# vcsklpf.net
KiCad netlist of a schematic drawn in EAGLE
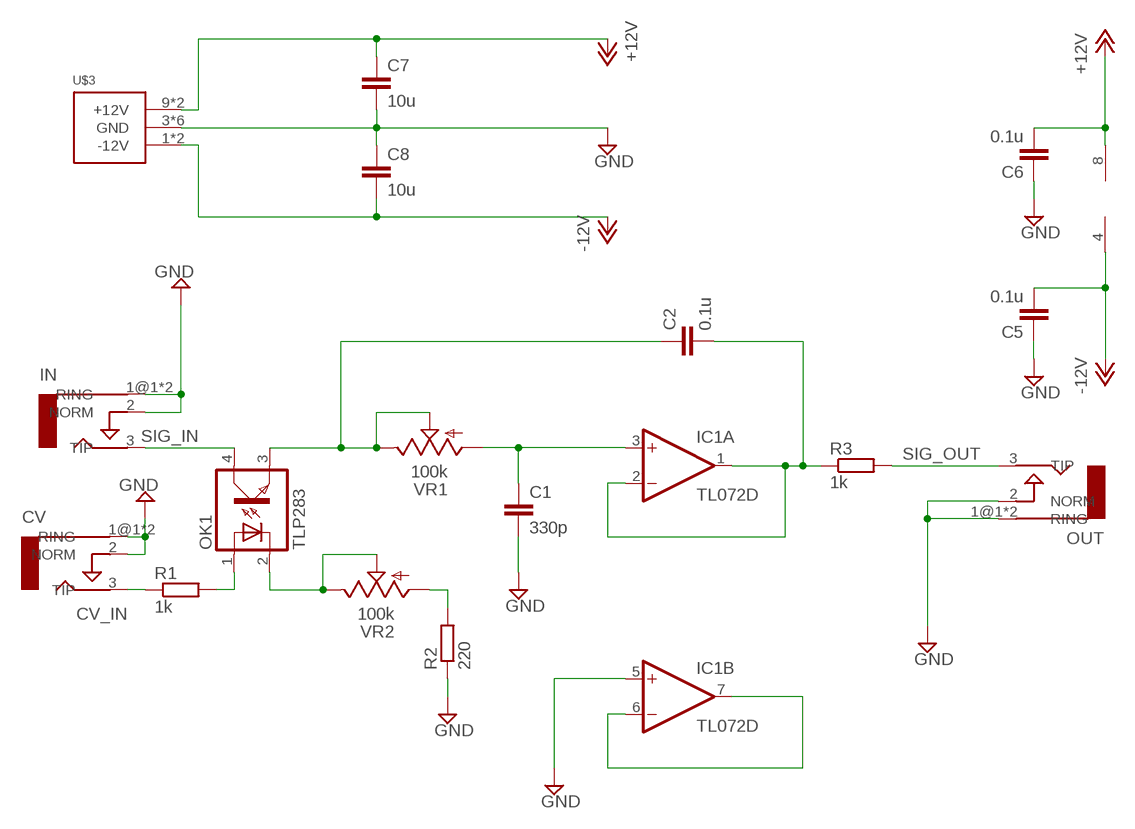
[diagram p0: schematic, sheet 1]

(export (version "E")
  (design (tool "Eeschema 10.0.6"))
  (components
    (comp (ref "C1")
      (value "330p")
      (footprint "eagle-import:C0805")
      (libsource (lib "eagle-import") (part "C-EUC0805"))
    )
    (comp (ref "C2")
      (value "0.1u")
      (footprint "eagle-import:C0805")
      (libsource (lib "eagle-import") (part "C-EUC0805"))
    )
    (comp (ref "C5")
      (value "0.1u")
      (footprint "eagle-import:C0805")
      (libsource (lib "eagle-import") (part "C-EUC0805"))
    )
    (comp (ref "C6")
      (value "0.1u")
      (footprint "eagle-import:C0805")
      (libsource (lib "eagle-import") (part "C-EUC0805"))
    )
    (comp (ref "C7")
      (value "10u")
      (footprint "eagle-import:C0805")
      (libsource (lib "eagle-import") (part "C-EUC0805"))
    )
    (comp (ref "C8")
      (value "10u")
      (footprint "eagle-import:C0805")
      (libsource (lib "eagle-import") (part "C-EUC0805"))
    )
    (comp (ref "CV")
      (value "AUDIO-JACKERTHENVAR")
      (footprint "eagle-import:ERTHENVAR-JACK")
      (libsource (lib "eagle-import") (part "AUDIO-JACKERTHENVAR"))
    )
    (comp (ref "IC1")
      (value "TL072D")
      (footprint "eagle-import:SO08")
      (libsource (lib "eagle-import") (part "TL072D"))
    )
    (comp (ref "IN")
      (value "AUDIO-JACKERTHENVAR")
      (footprint "eagle-import:ERTHENVAR-JACK")
      (libsource (lib "eagle-import") (part "AUDIO-JACKERTHENVAR"))
    )
    (comp (ref "OK1")
      (value "TLP283")
      (footprint "eagle-import:MINI-FLAT-4")
      (libsource (lib "eagle-import") (part "TLP283"))
    )
    (comp (ref "OUT")
      (value "AUDIO-JACKERTHENVAR")
      (footprint "eagle-import:ERTHENVAR-JACK")
      (libsource (lib "eagle-import") (part "AUDIO-JACKERTHENVAR"))
    )
    (comp (ref "R1")
      (value "1k")
      (footprint "eagle-import:R0805")
      (libsource (lib "eagle-import") (part "R-EU_R0805"))
    )
    (comp (ref "R2")
      (value "220")
      (footprint "eagle-import:R0805")
      (libsource (lib "eagle-import") (part "R-EU_R0805"))
    )
    (comp (ref "R3")
      (value "1k")
      (footprint "eagle-import:R0805")
      (libsource (lib "eagle-import") (part "R-EU_R0805"))
    )
    (comp (ref "U$3")
      (value "POWER_SIMPLE10")
      (footprint "eagle-import:POWER_10")
      (libsource (lib "eagle-import") (part "POWER_SIMPLE10"))
    )
    (comp (ref "VR1")
      (value "100k")
      (footprint "eagle-import:9MM_SNAP-IN_POT")
      (libsource (lib "eagle-import") (part "9MM_SNAP-IN_POT_"))
    )
    (comp (ref "VR2")
      (value "100k")
      (footprint "eagle-import:9MM_SNAP-IN_POT")
      (libsource (lib "eagle-import") (part "9MM_SNAP-IN_POT_"))
    )
  )
  (nets
    (net (code "1") (name "+12V") (class "Default")
      (node (ref "C6") (pin "2") (pinfunction "2_2") (pintype "passive"))
      (node (ref "C7") (pin "1") (pinfunction "1_1") (pintype "passive"))
      (node (ref "IC1") (pin "8") (pinfunction "V+_8") (pintype "power_in"))
      (node (ref "U$3") (pin "10") (pinfunction "+12V_10") (pintype "bidirectional"))
      (node (ref "U$3") (pin "9") (pinfunction "+12V_9") (pintype "bidirectional"))
    )
    (net (code "2") (name "-12V") (class "Default")
      (node (ref "C5") (pin "2") (pinfunction "2_2") (pintype "passive"))
      (node (ref "C8") (pin "2") (pinfunction "2_2") (pintype "passive"))
      (node (ref "IC1") (pin "4") (pinfunction "V-_4") (pintype "power_in"))
      (node (ref "U$3") (pin "1") (pinfunction "-12V_1") (pintype "bidirectional"))
      (node (ref "U$3") (pin "2") (pinfunction "-12V_2") (pintype "bidirectional"))
    )
    (net (code "3") (name "/CV_IN") (class "Default")
      (node (ref "CV") (pin "3") (pinfunction "TIP_3") (pintype "bidirectional"))
      (node (ref "R1") (pin "1") (pinfunction "1_1") (pintype "passive"))
    )
    (net (code "4") (name "/SIG_IN") (class "Default")
      (node (ref "IN") (pin "3") (pinfunction "TIP_3") (pintype "bidirectional"))
      (node (ref "OK1") (pin "4") (pinfunction "COL_4") (pintype "passive"))
    )
    (net (code "5") (name "/SIG_OUT") (class "Default")
      (node (ref "OUT") (pin "3") (pinfunction "TIP_3") (pintype "bidirectional"))
      (node (ref "R3") (pin "2") (pinfunction "2_2") (pintype "passive"))
    )
    (net (code "6") (name "GND") (class "Default")
      (node (ref "C1") (pin "2") (pinfunction "2_2") (pintype "passive"))
      (node (ref "C5") (pin "1") (pinfunction "1_1") (pintype "passive"))
      (node (ref "C6") (pin "1") (pinfunction "1_1") (pintype "passive"))
      (node (ref "C7") (pin "2") (pinfunction "2_2") (pintype "passive"))
      (node (ref "C8") (pin "1") (pinfunction "1_1") (pintype "passive"))
      (node (ref "CV") (pin "1@1") (pinfunction "RING_1@1") (pintype "bidirectional"))
      (node (ref "CV") (pin "1@2") (pinfunction "RING_1@2") (pintype "bidirectional"))
      (node (ref "CV") (pin "2") (pinfunction "NORM_2") (pintype "bidirectional"))
      (node (ref "IC1") (pin "5") (pinfunction "+IN_5") (pintype "input"))
      (node (ref "IN") (pin "1@1") (pinfunction "RING_1@1") (pintype "bidirectional"))
      (node (ref "IN") (pin "1@2") (pinfunction "RING_1@2") (pintype "bidirectional"))
      (node (ref "IN") (pin "2") (pinfunction "NORM_2") (pintype "bidirectional"))
      (node (ref "OUT") (pin "1@1") (pinfunction "RING_1@1") (pintype "bidirectional"))
      (node (ref "OUT") (pin "1@2") (pinfunction "RING_1@2") (pintype "bidirectional"))
      (node (ref "OUT") (pin "2") (pinfunction "NORM_2") (pintype "bidirectional"))
      (node (ref "R2") (pin "1") (pinfunction "1_1") (pintype "passive"))
      (node (ref "U$3") (pin "3") (pinfunction "GND_3") (pintype "bidirectional"))
      (node (ref "U$3") (pin "4") (pinfunction "GND_4") (pintype "bidirectional"))
      (node (ref "U$3") (pin "5") (pinfunction "GND_5") (pintype "bidirectional"))
      (node (ref "U$3") (pin "6") (pinfunction "GND_6") (pintype "bidirectional"))
      (node (ref "U$3") (pin "7") (pinfunction "GND_7") (pintype "bidirectional"))
      (node (ref "U$3") (pin "8") (pinfunction "GND_8") (pintype "bidirectional"))
    )
    (net (code "7") (name "Net-(IC1A-+IN)") (class "Default")
      (node (ref "C1") (pin "1") (pinfunction "1_1") (pintype "passive"))
      (node (ref "IC1") (pin "3") (pinfunction "+IN_3") (pintype "input"))
      (node (ref "VR1") (pin "1") (pinfunction "A_1") (pintype "passive"))
    )
    (net (code "8") (name "Net-(IC1A--IN)") (class "Default")
      (node (ref "C2") (pin "2") (pinfunction "2_2") (pintype "passive"))
      (node (ref "IC1") (pin "1") (pinfunction "OUT_1") (pintype "output"))
      (node (ref "IC1") (pin "2") (pinfunction "-IN_2") (pintype "input"))
      (node (ref "R3") (pin "1") (pinfunction "1_1") (pintype "passive"))
    )
    (net (code "9") (name "Net-(IC1B--IN)") (class "Default")
      (node (ref "IC1") (pin "6") (pinfunction "-IN_6") (pintype "input"))
      (node (ref "IC1") (pin "7") (pinfunction "OUT_7") (pintype "output"))
    )
    (net (code "10") (name "Net-(OK1-A)") (class "Default")
      (node (ref "OK1") (pin "1") (pinfunction "A_1") (pintype "passive"))
      (node (ref "R1") (pin "2") (pinfunction "2_2") (pintype "passive"))
    )
    (net (code "11") (name "Net-(OK1-C)") (class "Default")
      (node (ref "OK1") (pin "2") (pinfunction "C_2") (pintype "passive"))
      (node (ref "VR2") (pin "2") (pinfunction "S_2") (pintype "passive"))
      (node (ref "VR2") (pin "3") (pinfunction "E_3") (pintype "passive"))
    )
    (net (code "12") (name "Net-(OK1-EMIT)") (class "Default")
      (node (ref "C2") (pin "1") (pinfunction "1_1") (pintype "passive"))
      (node (ref "OK1") (pin "3") (pinfunction "EMIT_3") (pintype "passive"))
      (node (ref "VR1") (pin "2") (pinfunction "S_2") (pintype "passive"))
      (node (ref "VR1") (pin "3") (pinfunction "E_3") (pintype "passive"))
    )
    (net (code "13") (name "Net-(VR2-A)") (class "Default")
      (node (ref "R2") (pin "2") (pinfunction "2_2") (pintype "passive"))
      (node (ref "VR2") (pin "1") (pinfunction "A_1") (pintype "passive"))
    )
  )
)
